# SensWear_Haptic.net
KiCad netlist of a schematic drawn in Altium Designer
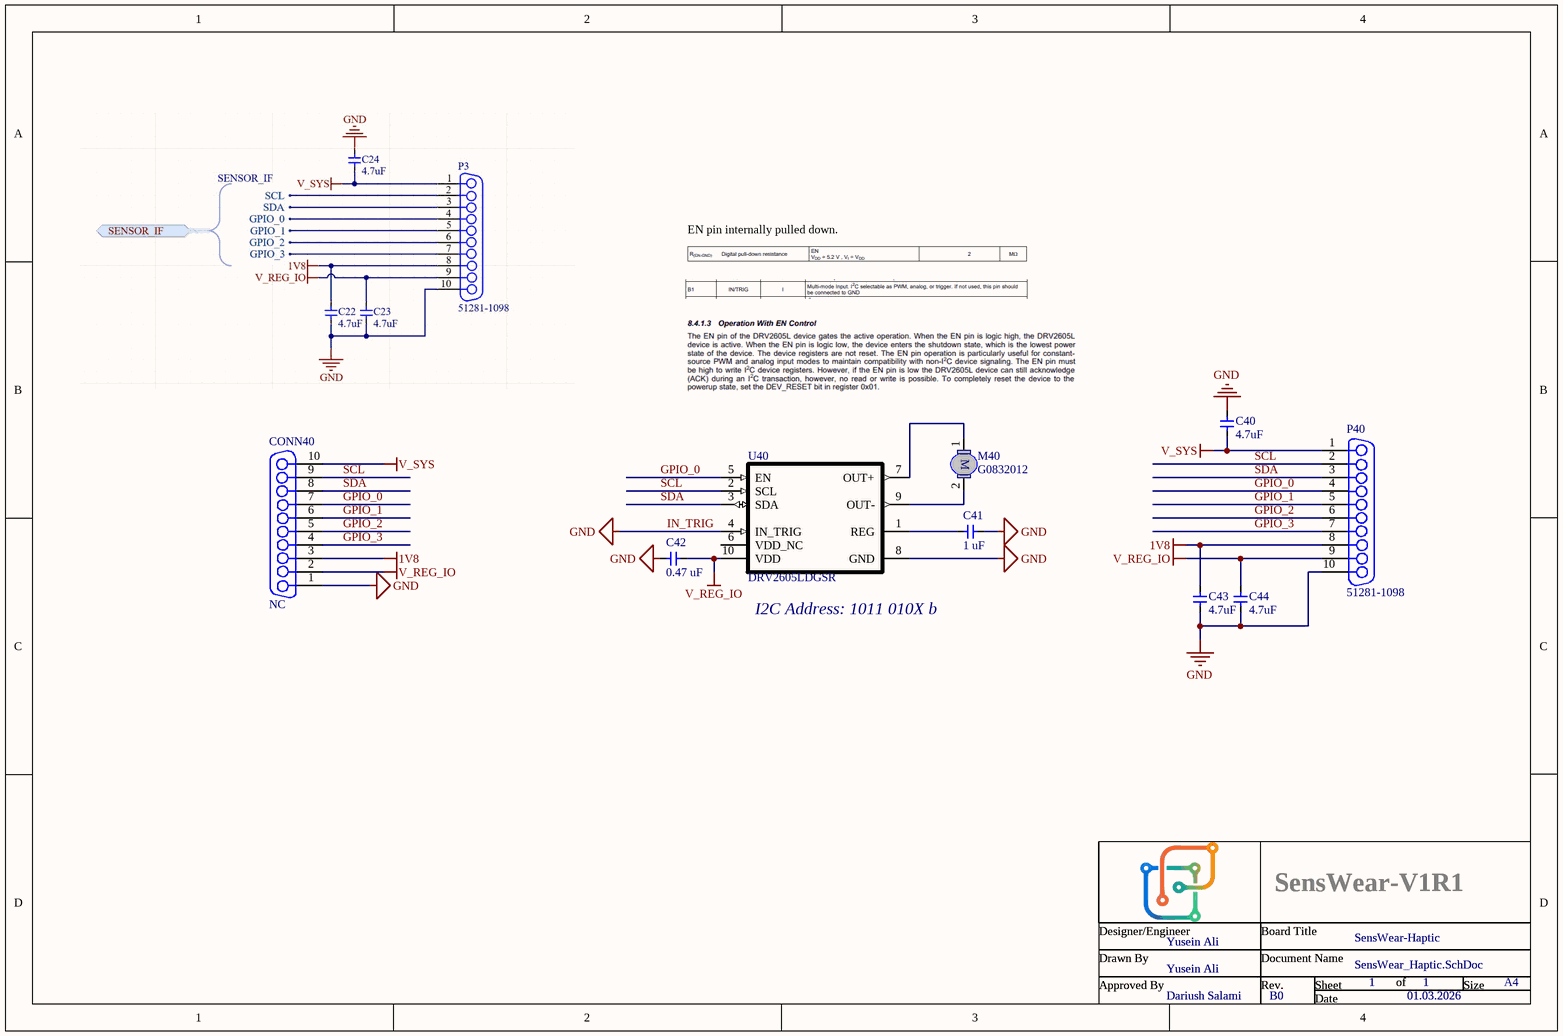
[diagram p0: SensWear_Haptic.SchDoc]

(export (version "E")
  (design (tool "Eeschema 10.0.6"))
  (components
    (comp (ref "C40")
      (value "4.7uF")
      (footprint "CAPC1005X05N")
      (description "Multilayer Ceramic Capacitor, 4.7 uF, 10 V, ± 20%, X5R, 0402 [1005 Metric]")
      (fields
        (field (name "MANUFACTURER") "Murata")
        (field (name "MANUFACTURER PART NUMBER") "GRM155R61A475MEAAD")
      )
      (libsource (lib "SensWearComponents") (part "GRM155R61A475MEAAD__2"))
    )
    (comp (ref "C41")
      (value "1 uF")
      (footprint "CAPC1005X05N")
      (description "CAP CER 1UF 10V X5R 0402")
      (fields
        (field (name "MANUFACTURER") "Murata Electronics North America")
        (field (name "MANUFACTURER PART NUMBER") "GRM155R61A105KE15D")
      )
      (libsource (lib "SensWearComponents") (part "GRM155R61A105KE15D__2"))
    )
    (comp (ref "C42")
      (value "0.47 uF")
      (footprint "CAPC1005X05N")
      (description "CAP CER 0.47UF 10V X5R 0402")
      (fields
        (field (name "MANUFACTURER") "Murata Electronics North America")
        (field (name "MANUFACTURER PART NUMBER") "GRM155R61A474KE15D")
      )
      (libsource (lib "SensWearComponents") (part "GRM155R61A474KE15D"))
    )
    (comp (ref "C43")
      (value "4.7uF")
      (footprint "CAPC1005X05N")
      (description "Multilayer Ceramic Capacitor, 4.7 uF, 10 V, ± 20%, X5R, 0402 [1005 Metric]")
      (fields
        (field (name "MANUFACTURER") "Murata")
        (field (name "MANUFACTURER PART NUMBER") "GRM155R61A475MEAAD")
      )
      (libsource (lib "SensWearComponents") (part "GRM155R61A475MEAAD__2"))
    )
    (comp (ref "C44")
      (value "4.7uF")
      (footprint "CAPC1005X05N")
      (description "Multilayer Ceramic Capacitor, 4.7 uF, 10 V, ± 20%, X5R, 0402 [1005 Metric]")
      (fields
        (field (name "MANUFACTURER") "Murata")
        (field (name "MANUFACTURER PART NUMBER") "GRM155R61A475MEAAD")
      )
      (libsource (lib "SensWearComponents") (part "GRM155R61A475MEAAD__2"))
    )
    (comp (ref "CONN40")
      (value "NC")
      (footprint "51281-1098-PCB")
      (libsource (lib "SensWearComponents") (part "51281-1098-PCB"))
    )
    (comp (ref "M40")
      (value "G0832012")
      (footprint "G0832012")
      (description "VIBRATION MOTOR 1.8V")
      (fields (field (name "MANUFACTURER") "Jinlong Machinery & Electronics, Inc."))
      (libsource (lib "SensWearComponents") (part "G0832012"))
    )
    (comp (ref "P40")
      (value "51281-1098")
      (footprint "51281-1098__3")
      (description "FFC/FPC Connector, Surface Mount, Right-Angle, Non-ZIF, Dual Contact Style")
      (fields (field (name "MANUFACTURER") "Molex"))
      (libsource (lib "SensWearComponents") (part "51281-1098__2"))
    )
    (comp (ref "U40")
      (value "DRV2605LDGSR")
      (footprint "TSSOP50P490X110-10N")
      (description "NEXT GEN DRV260X LRA/ERM DRIVER")
      (fields (field (name "MANUFACTURER") "Texas Instruments"))
      (libsource (lib "SensWearComponents") (part "DRV2605LDGSR"))
    )
  )
  (nets
    (net (code "1") (name "/GPIO_0") (class "Default")
      (node (ref "CONN40") (pin "7") (pinfunction "7_7") (pintype "passive"))
      (node (ref "P40") (pin "4") (pinfunction "4_4") (pintype "passive"))
      (node (ref "U40") (pin "5") (pinfunction "EN_5") (pintype "input"))
    )
    (net (code "2") (name "/GPIO_1") (class "Default")
      (node (ref "CONN40") (pin "6") (pinfunction "6_6") (pintype "passive"))
      (node (ref "P40") (pin "5") (pinfunction "5_5") (pintype "passive"))
    )
    (net (code "3") (name "/GPIO_2") (class "Default")
      (node (ref "CONN40") (pin "5") (pinfunction "5_5") (pintype "passive"))
      (node (ref "P40") (pin "6") (pinfunction "6_6") (pintype "passive"))
    )
    (net (code "4") (name "/GPIO_3") (class "Default")
      (node (ref "CONN40") (pin "4") (pinfunction "4_4") (pintype "passive"))
      (node (ref "P40") (pin "7") (pinfunction "7_7") (pintype "passive"))
    )
    (net (code "5") (name "/SCL") (class "Default")
      (node (ref "CONN40") (pin "9") (pinfunction "9_9") (pintype "passive"))
      (node (ref "P40") (pin "2") (pinfunction "2_2") (pintype "passive"))
      (node (ref "U40") (pin "2") (pinfunction "SCL_2") (pintype "input"))
    )
    (net (code "6") (name "/SDA") (class "Default")
      (node (ref "CONN40") (pin "8") (pinfunction "8_8") (pintype "passive"))
      (node (ref "P40") (pin "3") (pinfunction "3_3") (pintype "passive"))
      (node (ref "U40") (pin "3") (pinfunction "SDA_3") (pintype "bidirectional"))
    )
    (net (code "7") (name "1V8") (class "Default")
      (node (ref "C43") (pin "2") (pinfunction "2_2") (pintype "passive"))
      (node (ref "CONN40") (pin "3") (pinfunction "3_3") (pintype "passive"))
      (node (ref "P40") (pin "8") (pinfunction "8_8") (pintype "passive"))
    )
    (net (code "8") (name "GND") (class "Default")
      (node (ref "C40") (pin "2") (pinfunction "2_2") (pintype "passive"))
      (node (ref "C41") (pin "1") (pinfunction "1_1") (pintype "passive"))
      (node (ref "C42") (pin "2") (pinfunction "2_2") (pintype "passive"))
      (node (ref "C43") (pin "1") (pinfunction "1_1") (pintype "passive"))
      (node (ref "C44") (pin "1") (pinfunction "1_1") (pintype "passive"))
      (node (ref "CONN40") (pin "1") (pinfunction "1_1") (pintype "passive"))
      (node (ref "P40") (pin "10") (pinfunction "10_10") (pintype "passive"))
      (node (ref "U40") (pin "4") (pinfunction "IN_TRIG_4") (pintype "input"))
      (node (ref "U40") (pin "8") (pinfunction "GND_8") (pintype "power_in"))
    )
    (net (code "9") (name "Net-(U40-OUT+)") (class "Default")
      (node (ref "M40") (pin "1") (pinfunction "V+_1") (pintype "passive"))
      (node (ref "U40") (pin "7") (pinfunction "OUT+_7") (pintype "output"))
    )
    (net (code "10") (name "Net-(U40-OUT-)") (class "Default")
      (node (ref "M40") (pin "2") (pinfunction "V+_2") (pintype "passive"))
      (node (ref "U40") (pin "9") (pinfunction "OUT-_9") (pintype "output"))
    )
    (net (code "11") (name "Net-(U40-REG)") (class "Default")
      (node (ref "C41") (pin "2") (pinfunction "2_2") (pintype "passive"))
      (node (ref "U40") (pin "1") (pinfunction "REG_1") (pintype "power_in"))
    )
    (net (code "12") (name "V_REG_IO") (class "Default")
      (node (ref "C42") (pin "1") (pinfunction "1_1") (pintype "passive"))
      (node (ref "C44") (pin "2") (pinfunction "2_2") (pintype "passive"))
      (node (ref "CONN40") (pin "2") (pinfunction "2_2") (pintype "passive"))
      (node (ref "P40") (pin "9") (pinfunction "9_9") (pintype "passive"))
      (node (ref "U40") (pin "10") (pinfunction "VDD_10") (pintype "power_in"))
    )
    (net (code "13") (name "V_SYS") (class "Default")
      (node (ref "C40") (pin "1") (pinfunction "1_1") (pintype "passive"))
      (node (ref "CONN40") (pin "10") (pinfunction "10_10") (pintype "passive"))
      (node (ref "P40") (pin "1") (pinfunction "1_1") (pintype "passive"))
    )
    (net (code "14") (name "unconnected-(U40-VDD_NC-Pad6)") (class "Default")
      (node (ref "U40") (pin "6") (pinfunction "VDD_NC_6") (pintype "power_in"))
    )
  )
)
